# sensors.net
KiCad netlist of a schematic drawn in Altium Designer
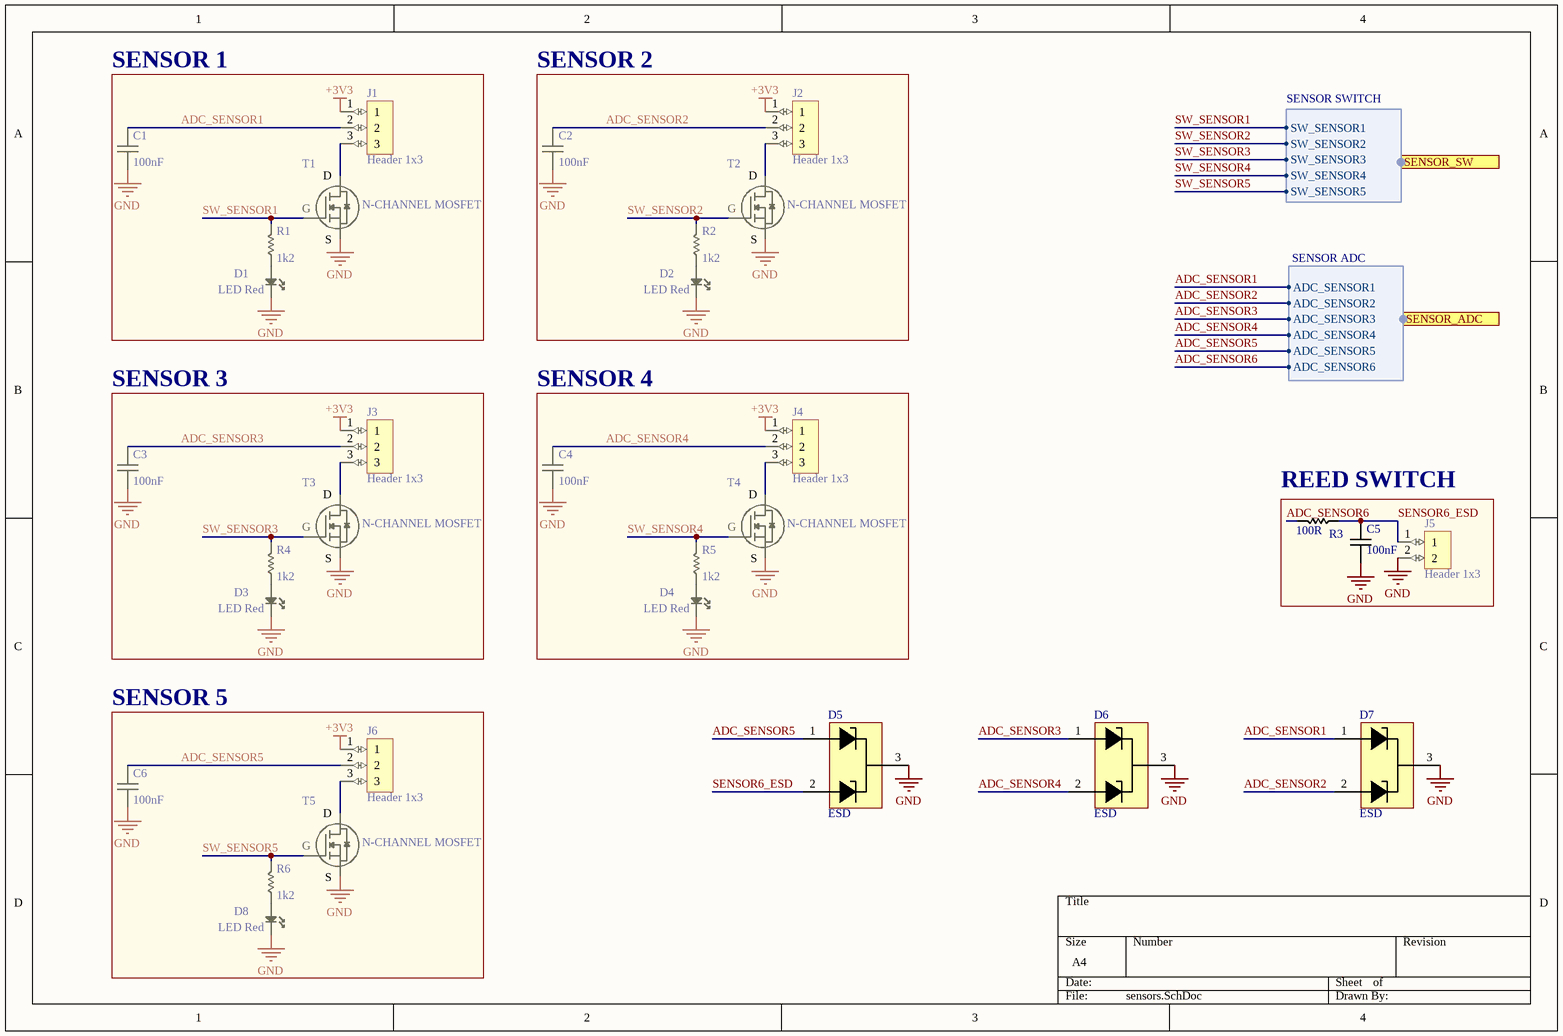
[diagram p0: sensors.SchDoc]

(export (version "E")
  (design (tool "Eeschema 10.0.6"))
  (components
    (comp (ref "C1")
      (value "100nF")
      (footprint "C0402")
      (fields (field (name "Comment") "Capacitor 0402"))
      (libsource (lib "altium-import") (part "root_1_Capacitor 0402_"))
    )
    (comp (ref "C2")
      (value "100nF")
      (footprint "C0402")
      (fields (field (name "Comment") "Capacitor 0402"))
      (libsource (lib "altium-import") (part "root_1_Capacitor 0402_"))
    )
    (comp (ref "C3")
      (value "100nF")
      (footprint "C0402")
      (fields (field (name "Comment") "Capacitor 0402"))
      (libsource (lib "altium-import") (part "root_1_Capacitor 0402_"))
    )
    (comp (ref "C4")
      (value "100nF")
      (footprint "C0402")
      (fields (field (name "Comment") "Capacitor 0402"))
      (libsource (lib "altium-import") (part "root_1_Capacitor 0402_"))
    )
    (comp (ref "C5")
      (value "100nF")
      (footprint "C0603")
      (fields (field (name "Comment") "Capacitor 0603"))
      (libsource (lib "Passive components") (part "Capacitor 0603"))
    )
    (comp (ref "C6")
      (value "100nF")
      (footprint "C0402")
      (fields (field (name "Comment") "Capacitor 0402"))
      (libsource (lib "altium-import") (part "root_1_Capacitor 0402_"))
    )
    (comp (ref "D1")
      (value "LED Red")
      (footprint "L0603 RED")
      (libsource (lib "altium-import") (part "root_3_LED 0603 Red_"))
    )
    (comp (ref "D2")
      (value "LED Red")
      (footprint "L0603 RED")
      (libsource (lib "altium-import") (part "root_3_LED 0603 Red_"))
    )
    (comp (ref "D3")
      (value "LED Red")
      (footprint "L0603 RED")
      (libsource (lib "altium-import") (part "root_3_LED 0603 Red_"))
    )
    (comp (ref "D4")
      (value "LED Red")
      (footprint "L0603 RED")
      (libsource (lib "altium-import") (part "root_3_LED 0603 Red_"))
    )
    (comp (ref "D5")
      (value "ESD")
      (footprint "ESD protection")
      (description "PESD3V3S2UAT")
      (libsource (lib "Transistors") (part "ESD protection 3.3V"))
    )
    (comp (ref "D6")
      (value "ESD")
      (footprint "ESD protection")
      (description "PESD3V3S2UAT")
      (libsource (lib "Transistors") (part "ESD protection 3.3V"))
    )
    (comp (ref "D7")
      (value "ESD")
      (footprint "ESD protection")
      (description "PESD3V3S2UAT")
      (libsource (lib "Transistors") (part "ESD protection 3.3V"))
    )
    (comp (ref "D8")
      (value "LED Red")
      (footprint "L0603 RED")
      (libsource (lib "altium-import") (part "root_3_LED 0603 Red_"))
    )
    (comp (ref "J1")
      (value "Header 1x3")
      (footprint "Header 1x3 Male JST")
      (libsource (lib "Connectors") (part "Header 1x3 Male"))
    )
    (comp (ref "J2")
      (value "Header 1x3")
      (footprint "Header 1x3 Male JST")
      (libsource (lib "Connectors") (part "Header 1x3 Male"))
    )
    (comp (ref "J3")
      (value "Header 1x3")
      (footprint "Header 1x3 Male JST")
      (libsource (lib "Connectors") (part "Header 1x3 Male"))
    )
    (comp (ref "J4")
      (value "Header 1x3")
      (footprint "Header 1x3 Male JST")
      (libsource (lib "Connectors") (part "Header 1x3 Male"))
    )
    (comp (ref "J5")
      (value "Header 1x3")
      (footprint "HEADER 1X2 MALE JST")
      (libsource (lib "Connectors") (part "Header 1x2 Male"))
    )
    (comp (ref "J6")
      (value "Header 1x3")
      (footprint "Header 1x3 Male JST")
      (libsource (lib "Connectors") (part "Header 1x3 Male"))
    )
    (comp (ref "R1")
      (value "1k2")
      (footprint "R0603")
      (fields (field (name "Comment") "Resistor 0603"))
      (libsource (lib "altium-import") (part "root_1_Resistor 0603_"))
    )
    (comp (ref "R2")
      (value "1k2")
      (footprint "R0603")
      (fields (field (name "Comment") "Resistor 0603"))
      (libsource (lib "altium-import") (part "root_1_Resistor 0603_"))
    )
    (comp (ref "R3")
      (value "100R")
      (footprint "R0603")
      (fields (field (name "Comment") "Resistor 0603"))
      (libsource (lib "altium-import") (part "root_2_Resistor 0603_"))
    )
    (comp (ref "R4")
      (value "1k2")
      (footprint "R0603")
      (fields (field (name "Comment") "Resistor 0603"))
      (libsource (lib "altium-import") (part "root_1_Resistor 0603_"))
    )
    (comp (ref "R5")
      (value "1k2")
      (footprint "R0603")
      (fields (field (name "Comment") "Resistor 0603"))
      (libsource (lib "altium-import") (part "root_1_Resistor 0603_"))
    )
    (comp (ref "R6")
      (value "1k2")
      (footprint "R0603")
      (fields (field (name "Comment") "Resistor 0603"))
      (libsource (lib "altium-import") (part "root_1_Resistor 0603_"))
    )
    (comp (ref "T1")
      (value "N-CHANNEL MOSFET")
      (footprint "2N7002")
      (libsource (lib "altium-import") (part "root_0_2N7002_"))
    )
    (comp (ref "T2")
      (value "N-CHANNEL MOSFET")
      (footprint "2N7002")
      (libsource (lib "altium-import") (part "root_0_2N7002_"))
    )
    (comp (ref "T3")
      (value "N-CHANNEL MOSFET")
      (footprint "2N7002")
      (libsource (lib "altium-import") (part "root_0_2N7002_"))
    )
    (comp (ref "T4")
      (value "N-CHANNEL MOSFET")
      (footprint "2N7002")
      (libsource (lib "altium-import") (part "root_0_2N7002_"))
    )
    (comp (ref "T5")
      (value "N-CHANNEL MOSFET")
      (footprint "2N7002")
      (libsource (lib "altium-import") (part "root_0_2N7002_"))
    )
  )
  (nets
    (net (code "4") (name "+3V3") (class "Default")
      (node (ref "J1") (pin "1") (pinfunction "1_1") (pintype "bidirectional"))
      (node (ref "J2") (pin "1") (pinfunction "1_1") (pintype "bidirectional"))
      (node (ref "J3") (pin "1") (pinfunction "1_1") (pintype "bidirectional"))
      (node (ref "J4") (pin "1") (pinfunction "1_1") (pintype "bidirectional"))
      (node (ref "J6") (pin "1") (pinfunction "1_1") (pintype "bidirectional"))
    )
    (net (code "5") (name "/ADC_SENSOR1") (class "Default")
      (node (ref "C1") (pin "2") (pinfunction "2_2") (pintype "passive"))
      (node (ref "D7") (pin "1") (pintype "passive"))
      (node (ref "J1") (pin "2") (pinfunction "2_2") (pintype "bidirectional"))
    )
    (net (code "6") (name "/ADC_SENSOR2") (class "Default")
      (node (ref "C2") (pin "2") (pinfunction "2_2") (pintype "passive"))
      (node (ref "D7") (pin "2") (pintype "passive"))
      (node (ref "J2") (pin "2") (pinfunction "2_2") (pintype "bidirectional"))
    )
    (net (code "7") (name "/ADC_SENSOR3") (class "Default")
      (node (ref "C3") (pin "2") (pinfunction "2_2") (pintype "passive"))
      (node (ref "D6") (pin "1") (pintype "passive"))
      (node (ref "J3") (pin "2") (pinfunction "2_2") (pintype "bidirectional"))
    )
    (net (code "8") (name "/ADC_SENSOR4") (class "Default")
      (node (ref "C4") (pin "2") (pinfunction "2_2") (pintype "passive"))
      (node (ref "D6") (pin "2") (pintype "passive"))
      (node (ref "J4") (pin "2") (pinfunction "2_2") (pintype "bidirectional"))
    )
    (net (code "9") (name "/ADC_SENSOR5") (class "Default")
      (node (ref "C6") (pin "2") (pinfunction "2_2") (pintype "passive"))
      (node (ref "D5") (pin "1") (pintype "passive"))
      (node (ref "J6") (pin "2") (pinfunction "2_2") (pintype "bidirectional"))
    )
    (net (code "10") (name "/ADC_SENSOR6") (class "Default")
      (node (ref "R3") (pin "2") (pinfunction "2_2") (pintype "passive"))
    )
    (net (code "11") (name "/SENSOR6_ESD") (class "Default")
      (node (ref "C5") (pin "2") (pinfunction "2_2") (pintype "passive"))
      (node (ref "D5") (pin "2") (pintype "passive"))
      (node (ref "J5") (pin "1") (pinfunction "1_1") (pintype "bidirectional"))
      (node (ref "R3") (pin "1") (pinfunction "1_1") (pintype "passive"))
    )
    (net (code "12") (name "/SW_SENSOR1") (class "Default")
      (node (ref "R1") (pin "2") (pinfunction "2_2") (pintype "passive"))
      (node (ref "T1") (pin "1") (pinfunction "G_1") (pintype "passive"))
    )
    (net (code "13") (name "/SW_SENSOR2") (class "Default")
      (node (ref "R2") (pin "2") (pinfunction "2_2") (pintype "passive"))
      (node (ref "T2") (pin "1") (pinfunction "G_1") (pintype "passive"))
    )
    (net (code "14") (name "/SW_SENSOR3") (class "Default")
      (node (ref "R4") (pin "2") (pinfunction "2_2") (pintype "passive"))
      (node (ref "T3") (pin "1") (pinfunction "G_1") (pintype "passive"))
    )
    (net (code "15") (name "/SW_SENSOR4") (class "Default")
      (node (ref "R5") (pin "2") (pinfunction "2_2") (pintype "passive"))
      (node (ref "T4") (pin "1") (pinfunction "G_1") (pintype "passive"))
    )
    (net (code "16") (name "/SW_SENSOR5") (class "Default")
      (node (ref "R6") (pin "2") (pinfunction "2_2") (pintype "passive"))
      (node (ref "T5") (pin "1") (pinfunction "G_1") (pintype "passive"))
    )
    (net (code "19") (name "GND") (class "Default")
      (node (ref "C1") (pin "1") (pinfunction "1_1") (pintype "passive"))
      (node (ref "C2") (pin "1") (pinfunction "1_1") (pintype "passive"))
      (node (ref "C3") (pin "1") (pinfunction "1_1") (pintype "passive"))
      (node (ref "C4") (pin "1") (pinfunction "1_1") (pintype "passive"))
      (node (ref "C5") (pin "1") (pinfunction "1_1") (pintype "passive"))
      (node (ref "C6") (pin "1") (pinfunction "1_1") (pintype "passive"))
      (node (ref "D1") (pin "2") (pinfunction "2_2") (pintype "passive"))
      (node (ref "D2") (pin "2") (pinfunction "2_2") (pintype "passive"))
      (node (ref "D3") (pin "2") (pinfunction "2_2") (pintype "passive"))
      (node (ref "D4") (pin "2") (pinfunction "2_2") (pintype "passive"))
      (node (ref "D5") (pin "3") (pintype "passive"))
      (node (ref "D6") (pin "3") (pintype "passive"))
      (node (ref "D7") (pin "3") (pintype "passive"))
      (node (ref "D8") (pin "2") (pinfunction "2_2") (pintype "passive"))
      (node (ref "J5") (pin "2") (pinfunction "2_2") (pintype "bidirectional"))
      (node (ref "T1") (pin "2") (pinfunction "S_2") (pintype "passive"))
      (node (ref "T2") (pin "2") (pinfunction "S_2") (pintype "passive"))
      (node (ref "T3") (pin "2") (pinfunction "S_2") (pintype "passive"))
      (node (ref "T4") (pin "2") (pinfunction "S_2") (pintype "passive"))
      (node (ref "T5") (pin "2") (pinfunction "S_2") (pintype "passive"))
    )
    (net (code "20") (name "Net-(D1-Pad1)") (class "Default")
      (node (ref "D1") (pin "1") (pinfunction "1_1") (pintype "passive"))
      (node (ref "R1") (pin "1") (pinfunction "1_1") (pintype "passive"))
    )
    (net (code "21") (name "Net-(D2-Pad1)") (class "Default")
      (node (ref "D2") (pin "1") (pinfunction "1_1") (pintype "passive"))
      (node (ref "R2") (pin "1") (pinfunction "1_1") (pintype "passive"))
    )
    (net (code "22") (name "Net-(D3-Pad1)") (class "Default")
      (node (ref "D3") (pin "1") (pinfunction "1_1") (pintype "passive"))
      (node (ref "R4") (pin "1") (pinfunction "1_1") (pintype "passive"))
    )
    (net (code "23") (name "Net-(D4-Pad1)") (class "Default")
      (node (ref "D4") (pin "1") (pinfunction "1_1") (pintype "passive"))
      (node (ref "R5") (pin "1") (pinfunction "1_1") (pintype "passive"))
    )
    (net (code "24") (name "Net-(D8-Pad1)") (class "Default")
      (node (ref "D8") (pin "1") (pinfunction "1_1") (pintype "passive"))
      (node (ref "R6") (pin "1") (pinfunction "1_1") (pintype "passive"))
    )
    (net (code "25") (name "Net-(T1-D)") (class "Default")
      (node (ref "J1") (pin "3") (pinfunction "3_3") (pintype "bidirectional"))
      (node (ref "T1") (pin "3") (pinfunction "D_3") (pintype "passive"))
    )
    (net (code "26") (name "Net-(T2-D)") (class "Default")
      (node (ref "J2") (pin "3") (pinfunction "3_3") (pintype "bidirectional"))
      (node (ref "T2") (pin "3") (pinfunction "D_3") (pintype "passive"))
    )
    (net (code "27") (name "Net-(T3-D)") (class "Default")
      (node (ref "J3") (pin "3") (pinfunction "3_3") (pintype "bidirectional"))
      (node (ref "T3") (pin "3") (pinfunction "D_3") (pintype "passive"))
    )
    (net (code "28") (name "Net-(T4-D)") (class "Default")
      (node (ref "J4") (pin "3") (pinfunction "3_3") (pintype "bidirectional"))
      (node (ref "T4") (pin "3") (pinfunction "D_3") (pintype "passive"))
    )
    (net (code "29") (name "Net-(T5-D)") (class "Default")
      (node (ref "J6") (pin "3") (pinfunction "3_3") (pintype "bidirectional"))
      (node (ref "T5") (pin "3") (pinfunction "D_3") (pintype "passive"))
    )
  )
)
